# switchPanel.net
KiCad netlist of a schematic drawn in Altium Designer
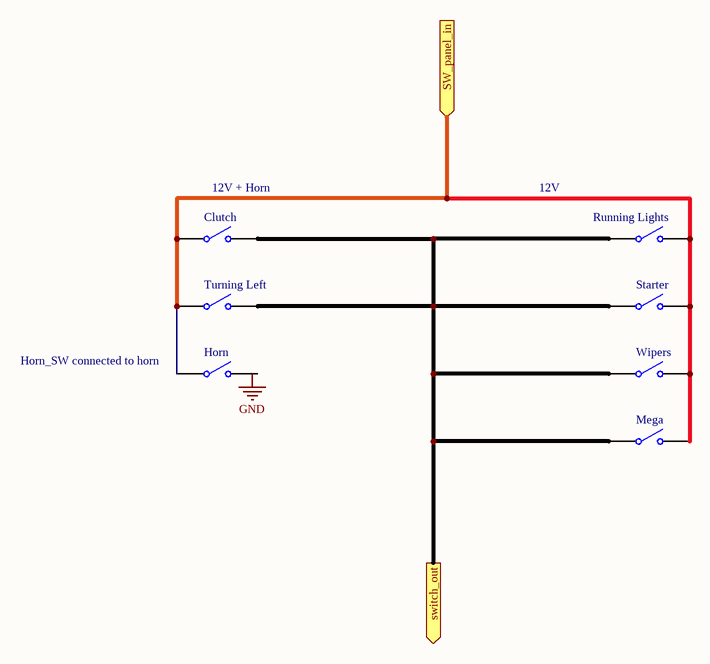
[diagram p0: switchPanel.SchDoc]

(export (version "E")
  (design (tool "Eeschema 10.0.6"))
  (components
    (comp (ref "Clutch")
      (value "SW-SPST")
      (footprint "SPST-2")
      (description "Single-Pole, Single-Throw Switch")
      (fields (field (name "PUBLISHER") "Altium Limited"))
      (libsource (lib "Miscellaneous Devices") (part "SW-SPST"))
    )
    (comp (ref "Horn")
      (value "SW-SPST")
      (footprint "SPST-2")
      (description "Single-Pole, Single-Throw Switch")
      (fields (field (name "PUBLISHER") "Altium Limited"))
      (libsource (lib "Miscellaneous Devices") (part "SW-SPST"))
    )
    (comp (ref "Mega")
      (value "SW-SPST")
      (footprint "SPST-2")
      (description "Single-Pole, Single-Throw Switch")
      (fields (field (name "PUBLISHER") "Altium Limited"))
      (libsource (lib "Miscellaneous Devices") (part "SW-SPST"))
    )
    (comp (ref "Running Lights")
      (value "SW-SPST")
      (footprint "SPST-2")
      (description "Single-Pole, Single-Throw Switch")
      (fields (field (name "PUBLISHER") "Altium Limited"))
      (libsource (lib "Miscellaneous Devices") (part "SW-SPST"))
    )
    (comp (ref "Starter")
      (value "SW-SPST")
      (footprint "SPST-2")
      (description "Single-Pole, Single-Throw Switch")
      (fields (field (name "PUBLISHER") "Altium Limited"))
      (libsource (lib "Miscellaneous Devices") (part "SW-SPST"))
    )
    (comp (ref "Turning Left")
      (value "SW-SPST")
      (footprint "SPST-2")
      (description "Single-Pole, Single-Throw Switch")
      (fields (field (name "PUBLISHER") "Altium Limited"))
      (libsource (lib "Miscellaneous Devices") (part "SW-SPST"))
    )
    (comp (ref "Wipers")
      (value "SW-SPST")
      (footprint "SPST-2")
      (description "Single-Pole, Single-Throw Switch")
      (fields (field (name "PUBLISHER") "Altium Limited"))
      (libsource (lib "Miscellaneous Devices") (part "SW-SPST"))
    )
  )
  (nets
    (net (code "1") (name "/SW_panel_in") (class "Default")
      (node (ref "Clutch") (pin "1") (pinfunction "COMMON_1") (pintype "passive"))
      (node (ref "Horn") (pin "1") (pinfunction "COMMON_1") (pintype "passive"))
      (node (ref "Mega") (pin "2") (pinfunction "NO_2") (pintype "passive"))
      (node (ref "Running Lights") (pin "2") (pinfunction "NO_2") (pintype "passive"))
      (node (ref "Starter") (pin "2") (pinfunction "NO_2") (pintype "passive"))
      (node (ref "Turning Left") (pin "1") (pinfunction "COMMON_1") (pintype "passive"))
      (node (ref "Wipers") (pin "2") (pinfunction "NO_2") (pintype "passive"))
    )
    (net (code "2") (name "/switch_out") (class "Default")
      (node (ref "Clutch") (pin "2") (pinfunction "NO_2") (pintype "passive"))
      (node (ref "Mega") (pin "1") (pinfunction "COMMON_1") (pintype "passive"))
      (node (ref "Running Lights") (pin "1") (pinfunction "COMMON_1") (pintype "passive"))
      (node (ref "Starter") (pin "1") (pinfunction "COMMON_1") (pintype "passive"))
      (node (ref "Turning Left") (pin "2") (pinfunction "NO_2") (pintype "passive"))
      (node (ref "Wipers") (pin "1") (pinfunction "COMMON_1") (pintype "passive"))
    )
    (net (code "4") (name "unconnected-(Horn-NO-Pad2)") (class "Default")
      (node (ref "Horn") (pin "2") (pinfunction "NO_2") (pintype "passive"))
    )
  )
)
